# Filter_Capacitors_-_Serial_Communication.net
KiCad netlist of a schematic drawn in Altium Designer
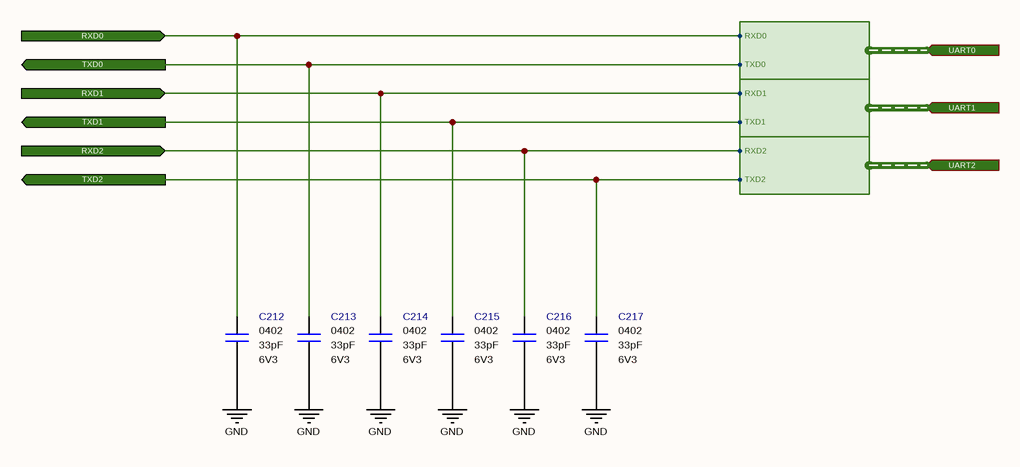
[diagram p0: Filter Capacitors - Serial Communication.SchDoc]

(export (version "E")
  (design (tool "Eeschema 10.0.6"))
  (components
    (comp (ref "C212")
      (value "33pF")
      (footprint "CAPACITOR_0402")
      (description "Capacitor - 33pF [0402] (Ceramic)")
      (fields
        (field (name "TOLERANCE") "10%")
        (field (name "CASE") "0402")
        (field (name "VOLTAGE") "6V3")
        (field (name "MANUFACTURER PART NUMBER") "C0402C330J9RACAUTO")
      )
      (libsource (lib "Ovoo_Library") (part "Capacitor - 33pF [0402-6V3]"))
    )
    (comp (ref "C213")
      (value "33pF")
      (footprint "CAPACITOR_0402")
      (description "Capacitor - 33pF [0402] (Ceramic)")
      (fields
        (field (name "TOLERANCE") "10%")
        (field (name "CASE") "0402")
        (field (name "VOLTAGE") "6V3")
        (field (name "MANUFACTURER PART NUMBER") "C0402C330J9RACAUTO")
      )
      (libsource (lib "Ovoo_Library") (part "Capacitor - 33pF [0402-6V3]"))
    )
    (comp (ref "C214")
      (value "33pF")
      (footprint "CAPACITOR_0402")
      (description "Capacitor - 33pF [0402] (Ceramic)")
      (fields
        (field (name "TOLERANCE") "10%")
        (field (name "CASE") "0402")
        (field (name "VOLTAGE") "6V3")
        (field (name "MANUFACTURER PART NUMBER") "C0402C330J9RACAUTO")
      )
      (libsource (lib "Ovoo_Library") (part "Capacitor - 33pF [0402-6V3]"))
    )
    (comp (ref "C215")
      (value "33pF")
      (footprint "CAPACITOR_0402")
      (description "Capacitor - 33pF [0402] (Ceramic)")
      (fields
        (field (name "TOLERANCE") "10%")
        (field (name "CASE") "0402")
        (field (name "VOLTAGE") "6V3")
        (field (name "MANUFACTURER PART NUMBER") "C0402C330J9RACAUTO")
      )
      (libsource (lib "Ovoo_Library") (part "Capacitor - 33pF [0402-6V3]"))
    )
    (comp (ref "C216")
      (value "33pF")
      (footprint "CAPACITOR_0402")
      (description "Capacitor - 33pF [0402] (Ceramic)")
      (fields
        (field (name "TOLERANCE") "10%")
        (field (name "CASE") "0402")
        (field (name "VOLTAGE") "6V3")
        (field (name "MANUFACTURER PART NUMBER") "C0402C330J9RACAUTO")
      )
      (libsource (lib "Ovoo_Library") (part "Capacitor - 33pF [0402-6V3]"))
    )
    (comp (ref "C217")
      (value "33pF")
      (footprint "CAPACITOR_0402")
      (description "Capacitor - 33pF [0402] (Ceramic)")
      (fields
        (field (name "TOLERANCE") "10%")
        (field (name "CASE") "0402")
        (field (name "VOLTAGE") "6V3")
        (field (name "MANUFACTURER PART NUMBER") "C0402C330J9RACAUTO")
      )
      (libsource (lib "Ovoo_Library") (part "Capacitor - 33pF [0402-6V3]"))
    )
  )
  (nets
    (net (code "4") (name "/RXD0") (class "Default")
      (node (ref "C212") (pin "2") (pinfunction "2_2") (pintype "passive"))
    )
    (net (code "5") (name "/RXD1") (class "Default")
      (node (ref "C214") (pin "2") (pinfunction "2_2") (pintype "passive"))
    )
    (net (code "6") (name "/RXD2") (class "Default")
      (node (ref "C216") (pin "2") (pinfunction "2_2") (pintype "passive"))
    )
    (net (code "7") (name "/TXD0") (class "Default")
      (node (ref "C213") (pin "2") (pinfunction "2_2") (pintype "passive"))
    )
    (net (code "8") (name "/TXD1") (class "Default")
      (node (ref "C215") (pin "2") (pinfunction "2_2") (pintype "passive"))
    )
    (net (code "9") (name "/TXD2") (class "Default")
      (node (ref "C217") (pin "2") (pinfunction "2_2") (pintype "passive"))
    )
    (net (code "13") (name "GND") (class "Default")
      (node (ref "C212") (pin "1") (pinfunction "1_1") (pintype "passive"))
      (node (ref "C213") (pin "1") (pinfunction "1_1") (pintype "passive"))
      (node (ref "C214") (pin "1") (pinfunction "1_1") (pintype "passive"))
      (node (ref "C215") (pin "1") (pinfunction "1_1") (pintype "passive"))
      (node (ref "C216") (pin "1") (pinfunction "1_1") (pintype "passive"))
      (node (ref "C217") (pin "1") (pinfunction "1_1") (pintype "passive"))
    )
  )
)
